# test.net
KiCad netlist of a schematic drawn in EAGLE
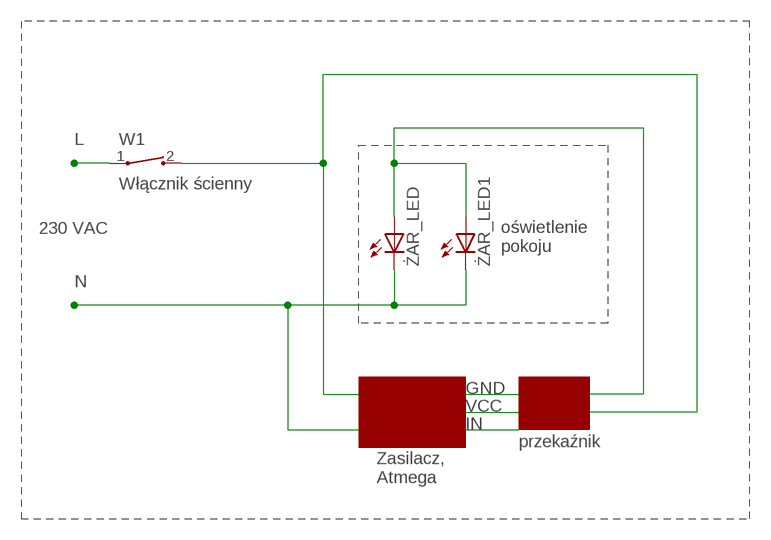
[diagram p0: schematic, sheet 1]

(export (version "E")
  (design (tool "Eeschema 10.0.6"))
  (components
    (comp (ref "W1")
      (value "Włącznik ścienny")
      (footprint "eagle-import:CT10-XXXX-G4")
      (libsource (lib "eagle-import") (part "CT10-XXXX-G4"))
    )
    (comp (ref "ŻAR_LED")
      (value "LEDB155")
      (footprint "eagle-import:Q62902-B155")
      (libsource (lib "eagle-import") (part "LEDB155"))
    )
    (comp (ref "ŻAR_LED1")
      (value "LEDB155")
      (footprint "eagle-import:Q62902-B155")
      (libsource (lib "eagle-import") (part "LEDB155"))
    )
  )
  (nets
    (net (code "1") (name "Net-(ŻAR_LED-C)") (class "Default")
      (node (ref "ŻAR_LED") (pin "K") (pinfunction "C_K") (pintype "passive"))
      (node (ref "ŻAR_LED1") (pin "K") (pinfunction "C_K") (pintype "passive"))
    )
    (net (code "2") (name "Net-(ŻAR_LED-PadA)") (class "Default")
      (node (ref "ŻAR_LED") (pin "A") (pinfunction "A_A") (pintype "passive"))
      (node (ref "ŻAR_LED1") (pin "A") (pinfunction "A_A") (pintype "passive"))
    )
    (net (code "3") (name "unconnected-(W1-Pad1)") (class "Default")
      (node (ref "W1") (pin "1") (pinfunction "1_1") (pintype "passive"))
    )
    (net (code "4") (name "unconnected-(W1-Pad2)") (class "Default")
      (node (ref "W1") (pin "2") (pinfunction "2_2") (pintype "passive"))
    )
  )
)
